# Main_capacitors.net
KiCad netlist of a schematic drawn in Altium Designer
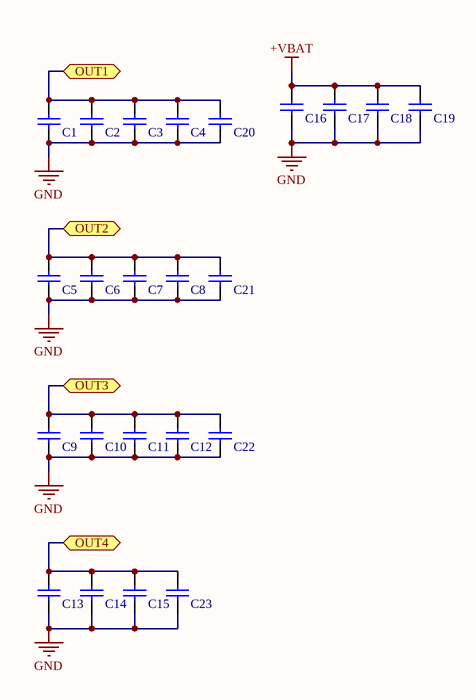
[diagram p0: Main_capacitors.SchDoc]

(export (version "E")
  (design (tool "Eeschema 10.0.6"))
  (components
    (comp (ref "C1")
      (value "Capacitor NP")
      (footprint "2512 CAP")
      (libsource (lib "IKSOR_LIB_main") (part "Capacitor NP"))
    )
    (comp (ref "C2")
      (value "Capacitor NP")
      (footprint "2512 CAP")
      (libsource (lib "IKSOR_LIB_main") (part "Capacitor NP"))
    )
    (comp (ref "C3")
      (value "Capacitor NP")
      (footprint "2512 CAP")
      (libsource (lib "IKSOR_LIB_main") (part "Capacitor NP"))
    )
    (comp (ref "C4")
      (value "Capacitor NP")
      (footprint "2512 CAP")
      (libsource (lib "IKSOR_LIB_main") (part "Capacitor NP"))
    )
    (comp (ref "C5")
      (value "Capacitor NP")
      (footprint "2512 CAP")
      (libsource (lib "IKSOR_LIB_main") (part "Capacitor NP"))
    )
    (comp (ref "C6")
      (value "Capacitor NP")
      (footprint "2512 CAP")
      (libsource (lib "IKSOR_LIB_main") (part "Capacitor NP"))
    )
    (comp (ref "C7")
      (value "Capacitor NP")
      (footprint "2512 CAP")
      (libsource (lib "IKSOR_LIB_main") (part "Capacitor NP"))
    )
    (comp (ref "C8")
      (value "Capacitor NP")
      (footprint "2512 CAP")
      (libsource (lib "IKSOR_LIB_main") (part "Capacitor NP"))
    )
    (comp (ref "C9")
      (value "Capacitor NP")
      (footprint "2512 CAP")
      (libsource (lib "IKSOR_LIB_main") (part "Capacitor NP"))
    )
    (comp (ref "C10")
      (value "Capacitor NP")
      (footprint "2512 CAP")
      (libsource (lib "IKSOR_LIB_main") (part "Capacitor NP"))
    )
    (comp (ref "C11")
      (value "Capacitor NP")
      (footprint "2512 CAP")
      (libsource (lib "IKSOR_LIB_main") (part "Capacitor NP"))
    )
    (comp (ref "C12")
      (value "Capacitor NP")
      (footprint "2512 CAP")
      (libsource (lib "IKSOR_LIB_main") (part "Capacitor NP"))
    )
    (comp (ref "C13")
      (value "Capacitor NP")
      (footprint "2512 CAP")
      (libsource (lib "IKSOR_LIB_main") (part "Capacitor NP"))
    )
    (comp (ref "C14")
      (value "Capacitor NP")
      (footprint "2512 CAP")
      (libsource (lib "IKSOR_LIB_main") (part "Capacitor NP"))
    )
    (comp (ref "C15")
      (value "Capacitor NP")
      (footprint "2512 CAP")
      (libsource (lib "IKSOR_LIB_main") (part "Capacitor NP"))
    )
    (comp (ref "C16")
      (value "Capacitor NP")
      (footprint "2512 CAP")
      (libsource (lib "IKSOR_LIB_main") (part "Capacitor NP"))
    )
    (comp (ref "C17")
      (value "Capacitor NP")
      (footprint "2512 CAP")
      (libsource (lib "IKSOR_LIB_main") (part "Capacitor NP"))
    )
    (comp (ref "C18")
      (value "Capacitor NP")
      (footprint "2512 CAP")
      (libsource (lib "IKSOR_LIB_main") (part "Capacitor NP"))
    )
    (comp (ref "C19")
      (value "Capacitor NP")
      (footprint "2512 CAP")
      (libsource (lib "IKSOR_LIB_main") (part "Capacitor NP"))
    )
    (comp (ref "C20")
      (value "Capacitor NP")
      (footprint "0805 CAP")
      (libsource (lib "IKSOR_LIB_main") (part "Capacitor NP"))
    )
    (comp (ref "C21")
      (value "Capacitor NP")
      (footprint "0805 CAP")
      (libsource (lib "IKSOR_LIB_main") (part "Capacitor NP"))
    )
    (comp (ref "C22")
      (value "Capacitor NP")
      (footprint "0805 CAP")
      (libsource (lib "IKSOR_LIB_main") (part "Capacitor NP"))
    )
    (comp (ref "C23")
      (value "Capacitor NP")
      (footprint "0805 CAP")
      (libsource (lib "IKSOR_LIB_main") (part "Capacitor NP"))
    )
  )
  (nets
    (net (code "1") (name "+VBAT") (class "Default")
      (node (ref "C16") (pin "2") (pinfunction "2_2") (pintype "passive"))
      (node (ref "C17") (pin "2") (pinfunction "2_2") (pintype "passive"))
      (node (ref "C18") (pin "2") (pinfunction "2_2") (pintype "passive"))
      (node (ref "C19") (pin "2") (pinfunction "2_2") (pintype "passive"))
    )
    (net (code "2") (name "/OUT1") (class "Default")
      (node (ref "C1") (pin "2") (pinfunction "2_2") (pintype "passive"))
      (node (ref "C2") (pin "2") (pinfunction "2_2") (pintype "passive"))
      (node (ref "C20") (pin "2") (pinfunction "2_2") (pintype "passive"))
      (node (ref "C3") (pin "2") (pinfunction "2_2") (pintype "passive"))
      (node (ref "C4") (pin "2") (pinfunction "2_2") (pintype "passive"))
    )
    (net (code "3") (name "/OUT2") (class "Default")
      (node (ref "C21") (pin "2") (pinfunction "2_2") (pintype "passive"))
      (node (ref "C5") (pin "2") (pinfunction "2_2") (pintype "passive"))
      (node (ref "C6") (pin "2") (pinfunction "2_2") (pintype "passive"))
      (node (ref "C7") (pin "2") (pinfunction "2_2") (pintype "passive"))
      (node (ref "C8") (pin "2") (pinfunction "2_2") (pintype "passive"))
    )
    (net (code "4") (name "/OUT3") (class "Default")
      (node (ref "C10") (pin "2") (pinfunction "2_2") (pintype "passive"))
      (node (ref "C11") (pin "2") (pinfunction "2_2") (pintype "passive"))
      (node (ref "C12") (pin "2") (pinfunction "2_2") (pintype "passive"))
      (node (ref "C22") (pin "2") (pinfunction "2_2") (pintype "passive"))
      (node (ref "C9") (pin "2") (pinfunction "2_2") (pintype "passive"))
    )
    (net (code "5") (name "/OUT4") (class "Default")
      (node (ref "C13") (pin "2") (pinfunction "2_2") (pintype "passive"))
      (node (ref "C14") (pin "2") (pinfunction "2_2") (pintype "passive"))
      (node (ref "C15") (pin "2") (pinfunction "2_2") (pintype "passive"))
      (node (ref "C23") (pin "2") (pinfunction "2_2") (pintype "passive"))
    )
    (net (code "6") (name "GND") (class "Default")
      (node (ref "C1") (pin "1") (pinfunction "1_1") (pintype "passive"))
      (node (ref "C10") (pin "1") (pinfunction "1_1") (pintype "passive"))
      (node (ref "C11") (pin "1") (pinfunction "1_1") (pintype "passive"))
      (node (ref "C12") (pin "1") (pinfunction "1_1") (pintype "passive"))
      (node (ref "C13") (pin "1") (pinfunction "1_1") (pintype "passive"))
      (node (ref "C14") (pin "1") (pinfunction "1_1") (pintype "passive"))
      (node (ref "C15") (pin "1") (pinfunction "1_1") (pintype "passive"))
      (node (ref "C16") (pin "1") (pinfunction "1_1") (pintype "passive"))
      (node (ref "C17") (pin "1") (pinfunction "1_1") (pintype "passive"))
      (node (ref "C18") (pin "1") (pinfunction "1_1") (pintype "passive"))
      (node (ref "C19") (pin "1") (pinfunction "1_1") (pintype "passive"))
      (node (ref "C2") (pin "1") (pinfunction "1_1") (pintype "passive"))
      (node (ref "C20") (pin "1") (pinfunction "1_1") (pintype "passive"))
      (node (ref "C21") (pin "1") (pinfunction "1_1") (pintype "passive"))
      (node (ref "C22") (pin "1") (pinfunction "1_1") (pintype "passive"))
      (node (ref "C23") (pin "1") (pinfunction "1_1") (pintype "passive"))
      (node (ref "C3") (pin "1") (pinfunction "1_1") (pintype "passive"))
      (node (ref "C4") (pin "1") (pinfunction "1_1") (pintype "passive"))
      (node (ref "C5") (pin "1") (pinfunction "1_1") (pintype "passive"))
      (node (ref "C6") (pin "1") (pinfunction "1_1") (pintype "passive"))
      (node (ref "C7") (pin "1") (pinfunction "1_1") (pintype "passive"))
      (node (ref "C8") (pin "1") (pinfunction "1_1") (pintype "passive"))
      (node (ref "C9") (pin "1") (pinfunction "1_1") (pintype "passive"))
    )
  )
)
